# main.net
KiCad netlist of a schematic drawn in EAGLE
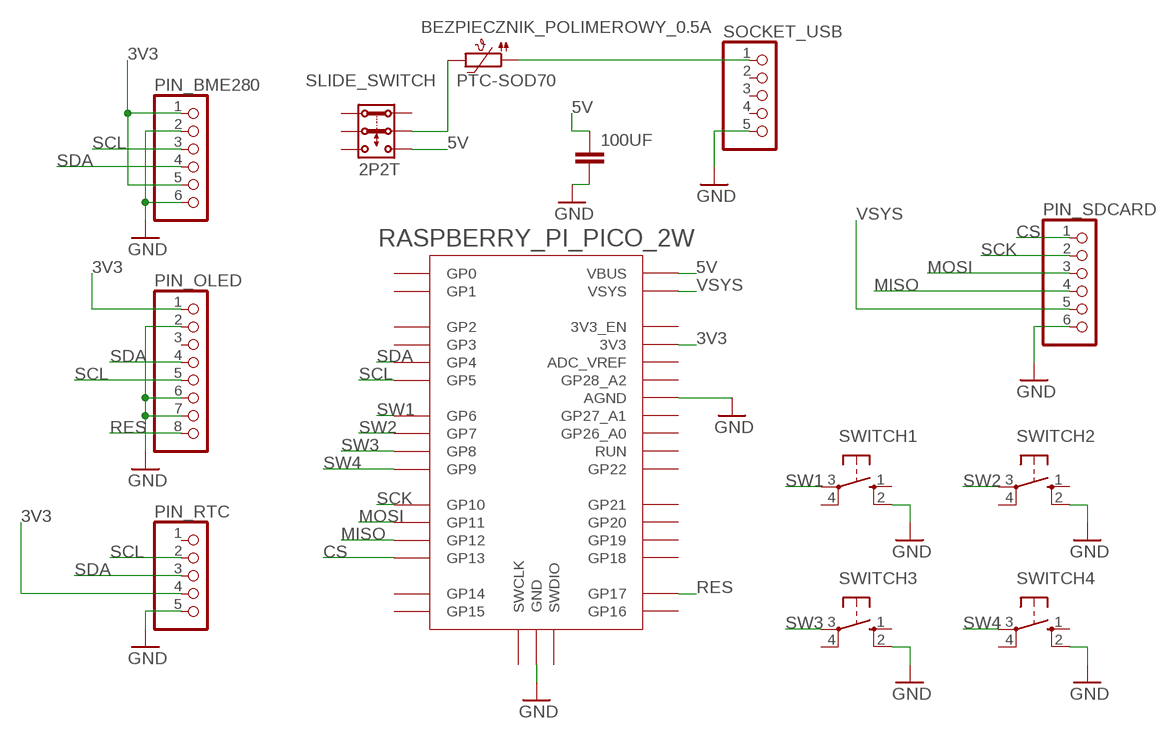
[diagram p0: schematic, sheet 1]

(export (version "E")
  (design (tool "Eeschema 10.0.6"))
  (components
    (comp (ref "100UF")
      (value "C2,5-3")
      (footprint "eagle-import:C2.5-3")
      (libsource (lib "eagle-import") (part "C2,5-3"))
    )
    (comp (ref "BEZPIECZNIK_POLIMEROWY_0.5A")
      (value "PTC-SOD70")
      (footprint "eagle-import:SOD70")
      (libsource (lib "eagle-import") (part "PTC-SOD70"))
    )
    (comp (ref "PIN_BME280")
      (value "PINHD-1X6")
      (footprint "eagle-import:1X06")
      (libsource (lib "eagle-import") (part "PINHD-1X6"))
    )
    (comp (ref "PIN_OLED")
      (value "PINHD-1X8")
      (footprint "eagle-import:1X08")
      (libsource (lib "eagle-import") (part "PINHD-1X8"))
    )
    (comp (ref "PIN_RTC")
      (value "PINHD-1X5")
      (footprint "eagle-import:1X05")
      (libsource (lib "eagle-import") (part "PINHD-1X5"))
    )
    (comp (ref "PIN_SDCARD")
      (value "PINHD-1X6")
      (footprint "eagle-import:1X06")
      (libsource (lib "eagle-import") (part "PINHD-1X6"))
    )
    (comp (ref "RASPBERRY_PI_PICO_2W")
      (value "RPI_PICO-TH")
      (footprint "eagle-import:RPI_PICO_TH")
      (libsource (lib "eagle-import") (part "RPI_PICO-TH"))
    )
    (comp (ref "SLIDE_SWITCH")
      (value "2P2T")
      (footprint "eagle-import:2P2T")
      (libsource (lib "eagle-import") (part "2P2T"))
    )
    (comp (ref "SOCKET_USB")
      (value "PINHD-1X5")
      (footprint "eagle-import:1X05")
      (libsource (lib "eagle-import") (part "PINHD-1X5"))
    )
    (comp (ref "SWITCH1")
      (value "10-XX")
      (footprint "eagle-import:B3F-10XX")
      (fields (field (name "MPN") "B3F-1000"))
      (libsource (lib "eagle-import") (part "10-XX"))
    )
    (comp (ref "SWITCH2")
      (value "10-XX")
      (footprint "eagle-import:B3F-10XX")
      (fields (field (name "MPN") "B3F-1000"))
      (libsource (lib "eagle-import") (part "10-XX"))
    )
    (comp (ref "SWITCH3")
      (value "10-XX")
      (footprint "eagle-import:B3F-10XX")
      (fields (field (name "MPN") "B3F-1000"))
      (libsource (lib "eagle-import") (part "10-XX"))
    )
    (comp (ref "SWITCH4")
      (value "10-XX")
      (footprint "eagle-import:B3F-10XX")
      (fields (field (name "MPN") "B3F-1000"))
      (libsource (lib "eagle-import") (part "10-XX"))
    )
  )
  (nets
    (net (code "1") (name "/3V3") (class "Default")
      (node (ref "PIN_BME280") (pin "1") (pinfunction "1_1") (pintype "passive"))
      (node (ref "PIN_BME280") (pin "5") (pinfunction "5_5") (pintype "passive"))
      (node (ref "PIN_OLED") (pin "1") (pinfunction "1_1") (pintype "passive"))
      (node (ref "PIN_RTC") (pin "4") (pinfunction "4_4") (pintype "passive"))
      (node (ref "RASPBERRY_PI_PICO_2W") (pin "3V3") (pinfunction "3V3_3V3") (pintype "bidirectional"))
    )
    (net (code "2") (name "/5V") (class "Default")
      (node (ref "100UF") (pin "1") (pinfunction "1_1") (pintype "passive"))
      (node (ref "RASPBERRY_PI_PICO_2W") (pin "VBUS") (pinfunction "VBUS_VBUS") (pintype "bidirectional"))
      (node (ref "SLIDE_SWITCH") (pin "3.1") (pinfunction "3.1_3.1") (pintype "passive"))
    )
    (net (code "3") (name "/CS") (class "Default")
      (node (ref "PIN_SDCARD") (pin "1") (pinfunction "1_1") (pintype "passive"))
      (node (ref "RASPBERRY_PI_PICO_2W") (pin "GP13") (pinfunction "GP13_GP13") (pintype "bidirectional"))
    )
    (net (code "4") (name "/MISO") (class "Default")
      (node (ref "PIN_SDCARD") (pin "4") (pinfunction "4_4") (pintype "passive"))
      (node (ref "RASPBERRY_PI_PICO_2W") (pin "GP12") (pinfunction "GP12_GP12") (pintype "bidirectional"))
    )
    (net (code "5") (name "/MOSI") (class "Default")
      (node (ref "PIN_SDCARD") (pin "3") (pinfunction "3_3") (pintype "passive"))
      (node (ref "RASPBERRY_PI_PICO_2W") (pin "GP11") (pinfunction "GP11_GP11") (pintype "bidirectional"))
    )
    (net (code "6") (name "/RES") (class "Default")
      (node (ref "PIN_OLED") (pin "8") (pinfunction "8_8") (pintype "passive"))
      (node (ref "RASPBERRY_PI_PICO_2W") (pin "GP17") (pinfunction "GP17_GP17") (pintype "bidirectional"))
    )
    (net (code "7") (name "/SCK") (class "Default")
      (node (ref "PIN_SDCARD") (pin "2") (pinfunction "2_2") (pintype "passive"))
      (node (ref "RASPBERRY_PI_PICO_2W") (pin "GP10") (pinfunction "GP10_GP10") (pintype "bidirectional"))
    )
    (net (code "8") (name "/SCL") (class "Default")
      (node (ref "PIN_BME280") (pin "3") (pinfunction "3_3") (pintype "passive"))
      (node (ref "PIN_OLED") (pin "5") (pinfunction "5_5") (pintype "passive"))
      (node (ref "PIN_RTC") (pin "2") (pinfunction "2_2") (pintype "passive"))
      (node (ref "RASPBERRY_PI_PICO_2W") (pin "GP5") (pinfunction "GP5_GP5") (pintype "bidirectional"))
    )
    (net (code "9") (name "/SDA") (class "Default")
      (node (ref "PIN_BME280") (pin "4") (pinfunction "4_4") (pintype "passive"))
      (node (ref "PIN_OLED") (pin "4") (pinfunction "4_4") (pintype "passive"))
      (node (ref "PIN_RTC") (pin "3") (pinfunction "3_3") (pintype "passive"))
      (node (ref "RASPBERRY_PI_PICO_2W") (pin "GP4") (pinfunction "GP4_GP4") (pintype "bidirectional"))
    )
    (net (code "10") (name "/SW1") (class "Default")
      (node (ref "RASPBERRY_PI_PICO_2W") (pin "GP6") (pinfunction "GP6_GP6") (pintype "bidirectional"))
      (node (ref "SWITCH1") (pin "3") (pinfunction "P_3") (pintype "passive"))
    )
    (net (code "11") (name "/SW2") (class "Default")
      (node (ref "RASPBERRY_PI_PICO_2W") (pin "GP7") (pinfunction "GP7_GP7") (pintype "bidirectional"))
      (node (ref "SWITCH2") (pin "3") (pinfunction "P_3") (pintype "passive"))
    )
    (net (code "12") (name "/SW3") (class "Default")
      (node (ref "RASPBERRY_PI_PICO_2W") (pin "GP8") (pinfunction "GP8_GP8") (pintype "bidirectional"))
      (node (ref "SWITCH3") (pin "3") (pinfunction "P_3") (pintype "passive"))
    )
    (net (code "13") (name "/SW4") (class "Default")
      (node (ref "RASPBERRY_PI_PICO_2W") (pin "GP9") (pinfunction "GP9_GP9") (pintype "bidirectional"))
      (node (ref "SWITCH4") (pin "3") (pinfunction "P_3") (pintype "passive"))
    )
    (net (code "14") (name "/VSYS") (class "Default")
      (node (ref "PIN_SDCARD") (pin "5") (pinfunction "5_5") (pintype "passive"))
      (node (ref "RASPBERRY_PI_PICO_2W") (pin "VSYS") (pinfunction "VSYS_VSYS") (pintype "bidirectional"))
    )
    (net (code "15") (name "GND") (class "Default")
      (node (ref "100UF") (pin "2") (pinfunction "2_2") (pintype "passive"))
      (node (ref "PIN_BME280") (pin "2") (pinfunction "2_2") (pintype "passive"))
      (node (ref "PIN_BME280") (pin "6") (pinfunction "6_6") (pintype "passive"))
      (node (ref "PIN_OLED") (pin "2") (pinfunction "2_2") (pintype "passive"))
      (node (ref "PIN_OLED") (pin "6") (pinfunction "6_6") (pintype "passive"))
      (node (ref "PIN_OLED") (pin "7") (pinfunction "7_7") (pintype "passive"))
      (node (ref "PIN_RTC") (pin "5") (pinfunction "5_5") (pintype "passive"))
      (node (ref "PIN_SDCARD") (pin "6") (pinfunction "6_6") (pintype "passive"))
      (node (ref "RASPBERRY_PI_PICO_2W") (pin "AGND") (pinfunction "AGND_AGND") (pintype "bidirectional"))
      (node (ref "RASPBERRY_PI_PICO_2W") (pin "GND@1") (pinfunction "GND_GND@1") (pintype "bidirectional"))
      (node (ref "RASPBERRY_PI_PICO_2W") (pin "GND@2") (pinfunction "GND_GND@2") (pintype "bidirectional"))
      (node (ref "RASPBERRY_PI_PICO_2W") (pin "GND@3") (pinfunction "GND_GND@3") (pintype "bidirectional"))
      (node (ref "RASPBERRY_PI_PICO_2W") (pin "GND@4") (pinfunction "GND_GND@4") (pintype "bidirectional"))
      (node (ref "RASPBERRY_PI_PICO_2W") (pin "GND@5") (pinfunction "GND_GND@5") (pintype "bidirectional"))
      (node (ref "RASPBERRY_PI_PICO_2W") (pin "GND@6") (pinfunction "GND_GND@6") (pintype "bidirectional"))
      (node (ref "RASPBERRY_PI_PICO_2W") (pin "GND@7") (pinfunction "GND_GND@7") (pintype "bidirectional"))
      (node (ref "RASPBERRY_PI_PICO_2W") (pin "GND@8") (pinfunction "GND_GND@8") (pintype "bidirectional"))
      (node (ref "SOCKET_USB") (pin "5") (pinfunction "5_5") (pintype "passive"))
      (node (ref "SWITCH1") (pin "2") (pinfunction "S1_2") (pintype "passive"))
      (node (ref "SWITCH2") (pin "2") (pinfunction "S1_2") (pintype "passive"))
      (node (ref "SWITCH3") (pin "2") (pinfunction "S1_2") (pintype "passive"))
      (node (ref "SWITCH4") (pin "2") (pinfunction "S1_2") (pintype "passive"))
    )
    (net (code "16") (name "Net-(BEZPIECZNIK_POLIMEROWY_0.5A-Pad1)") (class "Default")
      (node (ref "BEZPIECZNIK_POLIMEROWY_0.5A") (pin "1") (pinfunction "1_1") (pintype "passive"))
      (node (ref "SOCKET_USB") (pin "1") (pinfunction "1_1") (pintype "passive"))
    )
    (net (code "17") (name "Net-(BEZPIECZNIK_POLIMEROWY_0.5A-Pad2)") (class "Default")
      (node (ref "BEZPIECZNIK_POLIMEROWY_0.5A") (pin "2") (pinfunction "2_2") (pintype "passive"))
      (node (ref "SLIDE_SWITCH") (pin "2.1") (pinfunction "2.1_2.1") (pintype "passive"))
    )
    (net (code "18") (name "unconnected-(PIN_OLED-Pad3)") (class "Default")
      (node (ref "PIN_OLED") (pin "3") (pinfunction "3_3") (pintype "passive"))
    )
    (net (code "19") (name "unconnected-(PIN_RTC-Pad1)") (class "Default")
      (node (ref "PIN_RTC") (pin "1") (pinfunction "1_1") (pintype "passive"))
    )
    (net (code "20") (name "unconnected-(RASPBERRY_PI_PICO_2W-Pad3V3_EN)") (class "Default")
      (node (ref "RASPBERRY_PI_PICO_2W") (pin "3V3_EN") (pinfunction "3V3_EN_3V3_EN") (pintype "bidirectional"))
    )
    (net (code "21") (name "unconnected-(RASPBERRY_PI_PICO_2W-PadADC_VREF)") (class "Default")
      (node (ref "RASPBERRY_PI_PICO_2W") (pin "ADC_VREF") (pinfunction "ADC_VREF_ADC_VREF") (pintype "bidirectional"))
    )
    (net (code "22") (name "unconnected-(RASPBERRY_PI_PICO_2W-PadGP0)") (class "Default")
      (node (ref "RASPBERRY_PI_PICO_2W") (pin "GP0") (pinfunction "GP0_GP0") (pintype "bidirectional"))
    )
    (net (code "23") (name "unconnected-(RASPBERRY_PI_PICO_2W-PadGP1)") (class "Default")
      (node (ref "RASPBERRY_PI_PICO_2W") (pin "GP1") (pinfunction "GP1_GP1") (pintype "bidirectional"))
    )
    (net (code "24") (name "unconnected-(RASPBERRY_PI_PICO_2W-PadGP2)") (class "Default")
      (node (ref "RASPBERRY_PI_PICO_2W") (pin "GP2") (pinfunction "GP2_GP2") (pintype "bidirectional"))
    )
    (net (code "25") (name "unconnected-(RASPBERRY_PI_PICO_2W-PadGP3)") (class "Default")
      (node (ref "RASPBERRY_PI_PICO_2W") (pin "GP3") (pinfunction "GP3_GP3") (pintype "bidirectional"))
    )
    (net (code "26") (name "unconnected-(RASPBERRY_PI_PICO_2W-PadGP14)") (class "Default")
      (node (ref "RASPBERRY_PI_PICO_2W") (pin "GP14") (pinfunction "GP14_GP14") (pintype "bidirectional"))
    )
    (net (code "27") (name "unconnected-(RASPBERRY_PI_PICO_2W-PadGP15)") (class "Default")
      (node (ref "RASPBERRY_PI_PICO_2W") (pin "GP15") (pinfunction "GP15_GP15") (pintype "bidirectional"))
    )
    (net (code "28") (name "unconnected-(RASPBERRY_PI_PICO_2W-PadGP16)") (class "Default")
      (node (ref "RASPBERRY_PI_PICO_2W") (pin "GP16") (pinfunction "GP16_GP16") (pintype "bidirectional"))
    )
    (net (code "29") (name "unconnected-(RASPBERRY_PI_PICO_2W-PadGP18)") (class "Default")
      (node (ref "RASPBERRY_PI_PICO_2W") (pin "GP18") (pinfunction "GP18_GP18") (pintype "bidirectional"))
    )
    (net (code "30") (name "unconnected-(RASPBERRY_PI_PICO_2W-PadGP19)") (class "Default")
      (node (ref "RASPBERRY_PI_PICO_2W") (pin "GP19") (pinfunction "GP19_GP19") (pintype "bidirectional"))
    )
    (net (code "31") (name "unconnected-(RASPBERRY_PI_PICO_2W-PadGP20)") (class "Default")
      (node (ref "RASPBERRY_PI_PICO_2W") (pin "GP20") (pinfunction "GP20_GP20") (pintype "bidirectional"))
    )
    (net (code "32") (name "unconnected-(RASPBERRY_PI_PICO_2W-PadGP21)") (class "Default")
      (node (ref "RASPBERRY_PI_PICO_2W") (pin "GP21") (pinfunction "GP21_GP21") (pintype "bidirectional"))
    )
    (net (code "33") (name "unconnected-(RASPBERRY_PI_PICO_2W-PadGP22)") (class "Default")
      (node (ref "RASPBERRY_PI_PICO_2W") (pin "GP22") (pinfunction "GP22_GP22") (pintype "bidirectional"))
    )
    (net (code "34") (name "unconnected-(RASPBERRY_PI_PICO_2W-PadGP26_A0)") (class "Default")
      (node (ref "RASPBERRY_PI_PICO_2W") (pin "GP26_A0") (pinfunction "GP26_A0_GP26_A0") (pintype "bidirectional"))
    )
    (net (code "35") (name "unconnected-(RASPBERRY_PI_PICO_2W-PadGP27_A1)") (class "Default")
      (node (ref "RASPBERRY_PI_PICO_2W") (pin "GP27_A1") (pinfunction "GP27_A1_GP27_A1") (pintype "bidirectional"))
    )
    (net (code "36") (name "unconnected-(RASPBERRY_PI_PICO_2W-PadGP28_A2)") (class "Default")
      (node (ref "RASPBERRY_PI_PICO_2W") (pin "GP28_A2") (pinfunction "GP28_A2_GP28_A2") (pintype "bidirectional"))
    )
    (net (code "37") (name "unconnected-(RASPBERRY_PI_PICO_2W-PadRUN)") (class "Default")
      (node (ref "RASPBERRY_PI_PICO_2W") (pin "RUN") (pinfunction "RUN_RUN") (pintype "bidirectional"))
    )
    (net (code "38") (name "unconnected-(RASPBERRY_PI_PICO_2W-PadSWCLK)") (class "Default")
      (node (ref "RASPBERRY_PI_PICO_2W") (pin "SWCLK") (pinfunction "SWCLK_SWCLK") (pintype "bidirectional"))
    )
    (net (code "39") (name "unconnected-(RASPBERRY_PI_PICO_2W-PadSWDIO)") (class "Default")
      (node (ref "RASPBERRY_PI_PICO_2W") (pin "SWDIO") (pinfunction "SWDIO_SWDIO") (pintype "bidirectional"))
    )
    (net (code "40") (name "unconnected-(SLIDE_SWITCH-Pad1.1)") (class "Default")
      (node (ref "SLIDE_SWITCH") (pin "1.1") (pinfunction "1.1_1.1") (pintype "passive"))
    )
    (net (code "41") (name "unconnected-(SLIDE_SWITCH-Pad1.2)") (class "Default")
      (node (ref "SLIDE_SWITCH") (pin "1.2") (pinfunction "1.2_1.2") (pintype "passive"))
    )
    (net (code "42") (name "unconnected-(SLIDE_SWITCH-Pad2.2)") (class "Default")
      (node (ref "SLIDE_SWITCH") (pin "2.2") (pinfunction "2.2_2.2") (pintype "passive"))
    )
    (net (code "43") (name "unconnected-(SLIDE_SWITCH-Pad3.2)") (class "Default")
      (node (ref "SLIDE_SWITCH") (pin "3.2") (pinfunction "3.2_3.2") (pintype "passive"))
    )
    (net (code "44") (name "unconnected-(SOCKET_USB-Pad2)") (class "Default")
      (node (ref "SOCKET_USB") (pin "2") (pinfunction "2_2") (pintype "passive"))
    )
    (net (code "45") (name "unconnected-(SOCKET_USB-Pad3)") (class "Default")
      (node (ref "SOCKET_USB") (pin "3") (pinfunction "3_3") (pintype "passive"))
    )
    (net (code "46") (name "unconnected-(SOCKET_USB-Pad4)") (class "Default")
      (node (ref "SOCKET_USB") (pin "4") (pinfunction "4_4") (pintype "passive"))
    )
    (net (code "47") (name "unconnected-(SWITCH1-P1-Pad4)") (class "Default")
      (node (ref "SWITCH1") (pin "4") (pinfunction "P1_4") (pintype "passive"))
    )
    (net (code "48") (name "unconnected-(SWITCH1-S-Pad1)") (class "Default")
      (node (ref "SWITCH1") (pin "1") (pinfunction "S_1") (pintype "passive"))
    )
    (net (code "49") (name "unconnected-(SWITCH2-P1-Pad4)") (class "Default")
      (node (ref "SWITCH2") (pin "4") (pinfunction "P1_4") (pintype "passive"))
    )
    (net (code "50") (name "unconnected-(SWITCH2-S-Pad1)") (class "Default")
      (node (ref "SWITCH2") (pin "1") (pinfunction "S_1") (pintype "passive"))
    )
    (net (code "51") (name "unconnected-(SWITCH3-P1-Pad4)") (class "Default")
      (node (ref "SWITCH3") (pin "4") (pinfunction "P1_4") (pintype "passive"))
    )
    (net (code "52") (name "unconnected-(SWITCH3-S-Pad1)") (class "Default")
      (node (ref "SWITCH3") (pin "1") (pinfunction "S_1") (pintype "passive"))
    )
    (net (code "53") (name "unconnected-(SWITCH4-P1-Pad4)") (class "Default")
      (node (ref "SWITCH4") (pin "4") (pinfunction "P1_4") (pintype "passive"))
    )
    (net (code "54") (name "unconnected-(SWITCH4-S-Pad1)") (class "Default")
      (node (ref "SWITCH4") (pin "1") (pinfunction "S_1") (pintype "passive"))
    )
  )
)
